# D5035-01.net
KiCad netlist of a schematic drawn in Altium Designer
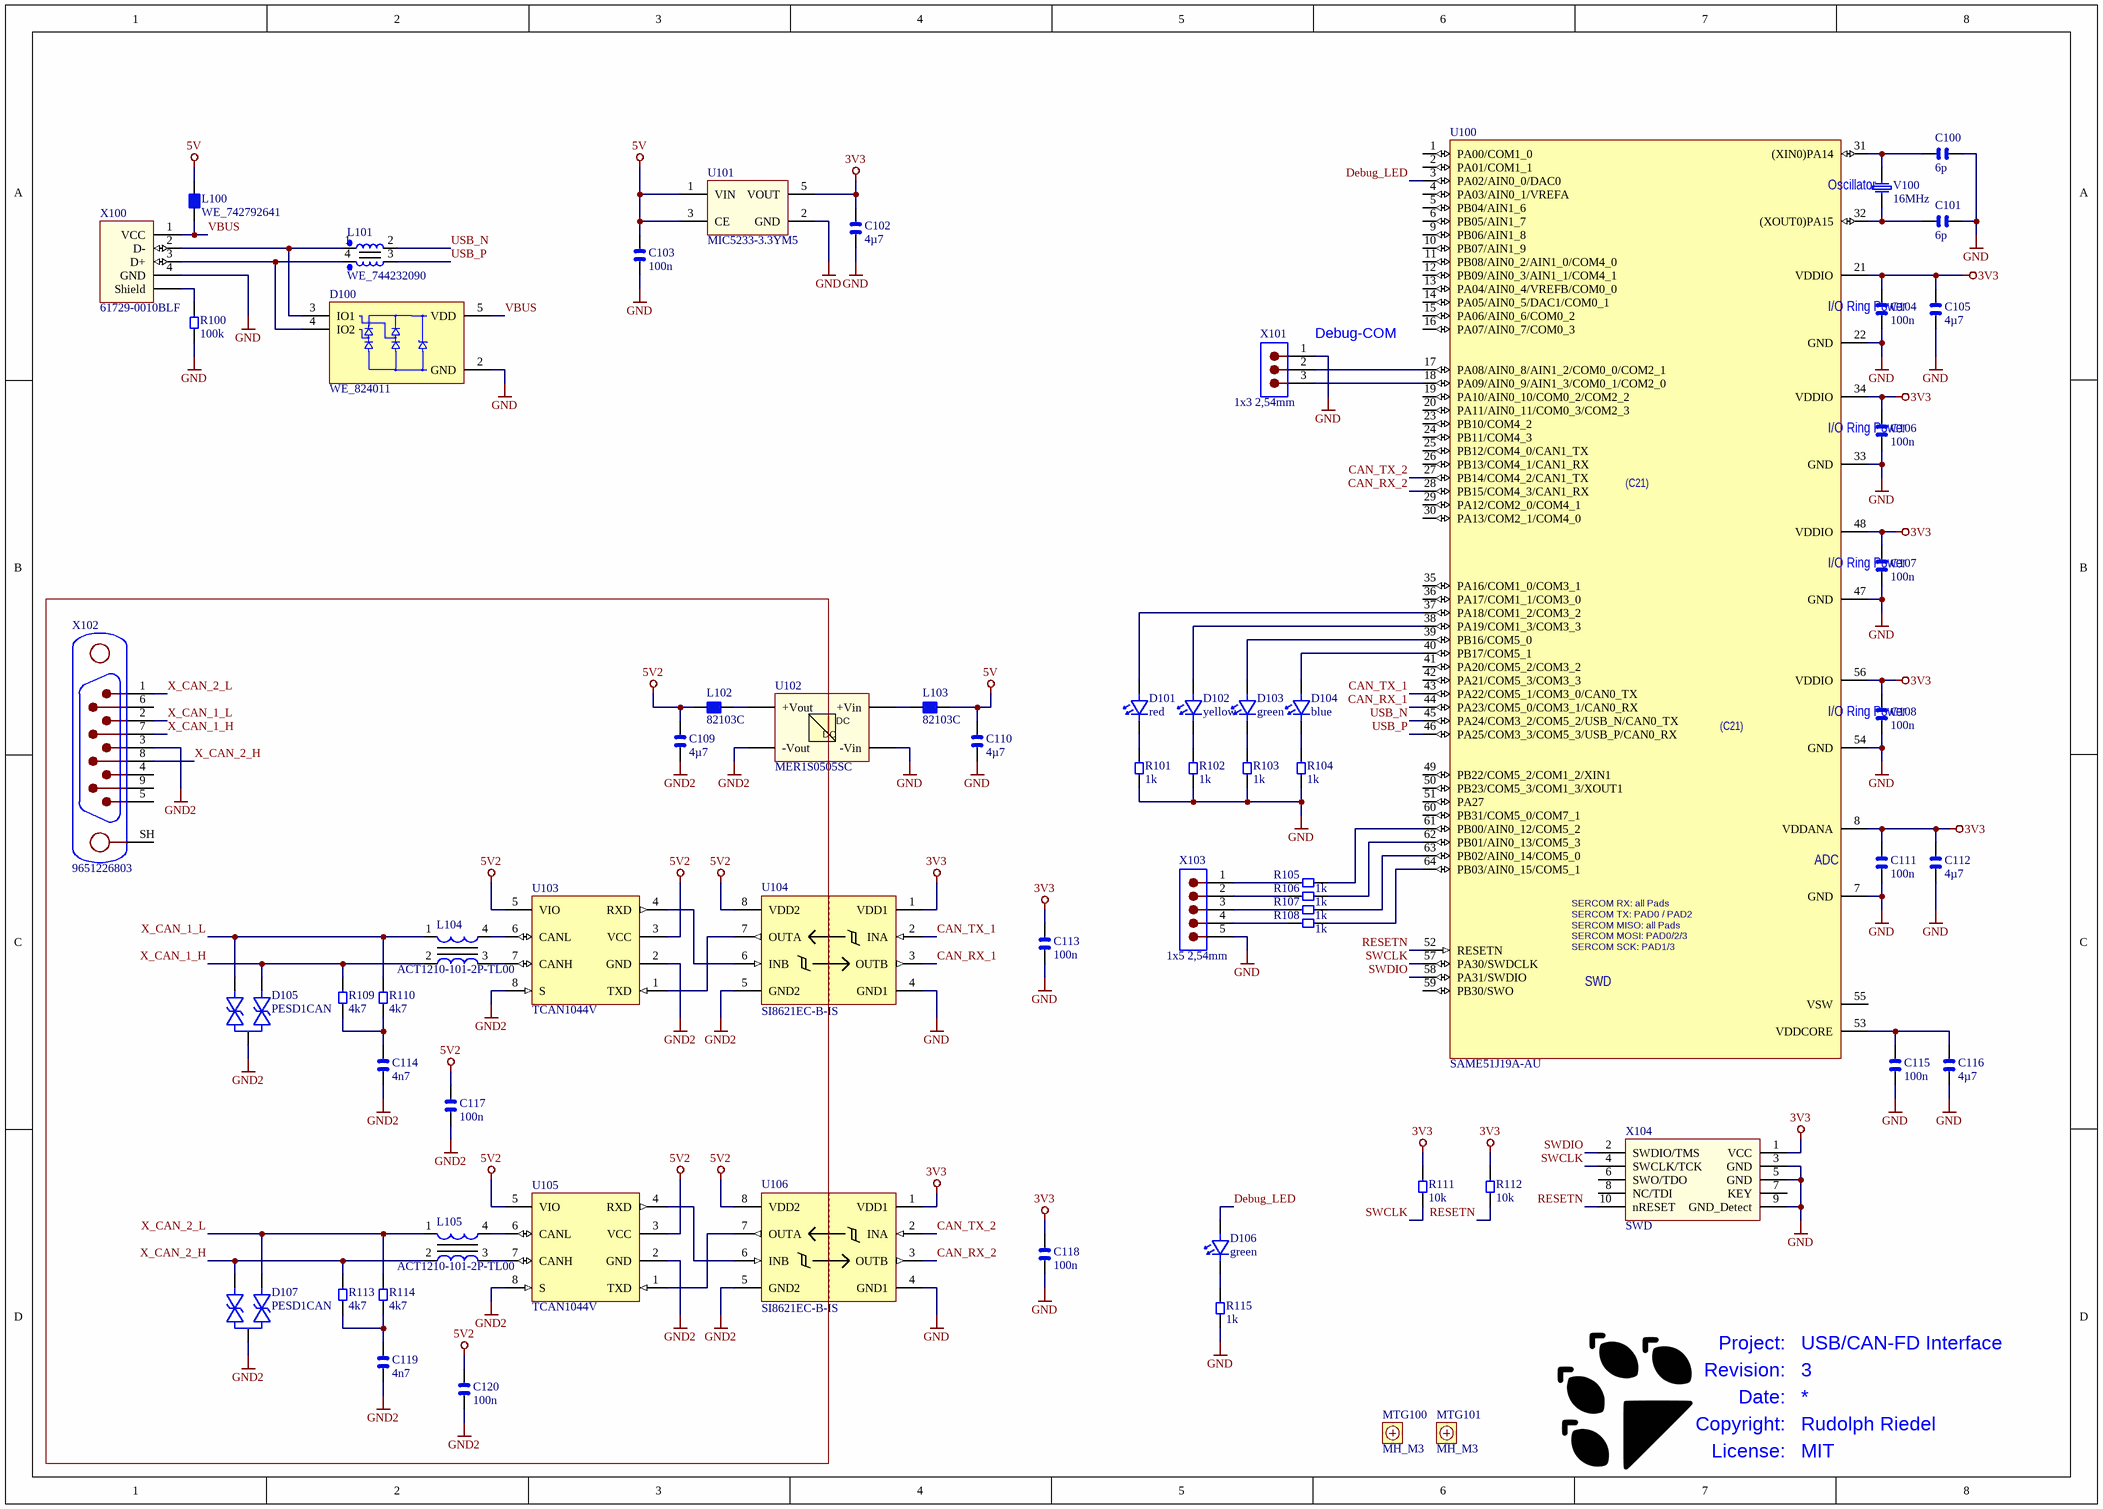
[diagram p0: D5035-01.SchDoc]

(export (version "E")
  (design (tool "Eeschema 10.0.6"))
  (components
    (comp (ref "C100")
      (value "6p")
      (footprint "CAPC1608X09L")
      (description "0603 Chip Capacitor")
      (fields (field (name "PART NUMBER") "CAPC_0603") (field (name "EDITOR") "rriedel"))
      (libsource (lib "HW-Labor_GF") (part "CAP_2_V2"))
    )
    (comp (ref "C101")
      (value "6p")
      (footprint "CAPC1608X09L")
      (description "0603 Chip Capacitor")
      (fields (field (name "PART NUMBER") "CAPC_0603") (field (name "EDITOR") "rriedel"))
      (libsource (lib "HW-Labor_GF") (part "CAP_2_V2"))
    )
    (comp (ref "C102")
      (value "4µ7")
      (footprint "CAPC2012X14L")
      (description "0805 Chip Capacitor")
      (fields (field (name "PART NUMBER") "CAPC_0805") (field (name "EDITOR") "rriedel"))
      (libsource (lib "HW-Labor_GF") (part "CAP_2_V2"))
    )
    (comp (ref "C103")
      (value "100n")
      (footprint "CAPC1608X09L")
      (description "0603 Chip Capacitor")
      (fields (field (name "PART NUMBER") "CAPC_0603") (field (name "EDITOR") "rriedel"))
      (libsource (lib "HW-Labor_GF") (part "CAP_2_V2"))
    )
    (comp (ref "C104")
      (value "100n")
      (footprint "CAPC1608X09L")
      (description "0603 Chip Capacitor")
      (fields (field (name "PART NUMBER") "CAPC_0603") (field (name "EDITOR") "rriedel"))
      (libsource (lib "HW-Labor_GF") (part "CAP_2_V2"))
    )
    (comp (ref "C105")
      (value "4µ7")
      (footprint "CAPC2012X14L")
      (description "0805 Chip Capacitor")
      (fields (field (name "PART NUMBER") "CAPC_0805") (field (name "EDITOR") "rriedel"))
      (libsource (lib "HW-Labor_GF") (part "CAP_2_V2"))
    )
    (comp (ref "C106")
      (value "100n")
      (footprint "CAPC1608X09L")
      (description "0603 Chip Capacitor")
      (fields (field (name "PART NUMBER") "CAPC_0603") (field (name "EDITOR") "rriedel"))
      (libsource (lib "HW-Labor_GF") (part "CAP_2_V2"))
    )
    (comp (ref "C107")
      (value "100n")
      (footprint "CAPC1608X09L")
      (description "0603 Chip Capacitor")
      (fields (field (name "PART NUMBER") "CAPC_0603") (field (name "EDITOR") "rriedel"))
      (libsource (lib "HW-Labor_GF") (part "CAP_2_V2"))
    )
    (comp (ref "C108")
      (value "100n")
      (footprint "CAPC1608X09L")
      (description "0603 Chip Capacitor")
      (fields (field (name "PART NUMBER") "CAPC_0603") (field (name "EDITOR") "rriedel"))
      (libsource (lib "HW-Labor_GF") (part "CAP_2_V2"))
    )
    (comp (ref "C109")
      (value "4µ7")
      (footprint "CAPC2012X14L")
      (description "0805 Chip Capacitor")
      (fields (field (name "PART NUMBER") "CAPC_0805") (field (name "EDITOR") "rriedel"))
      (libsource (lib "HW-Labor_GF") (part "CAP_2_V2"))
    )
    (comp (ref "C110")
      (value "4µ7")
      (footprint "CAPC2012X14L")
      (description "0805 Chip Capacitor")
      (fields (field (name "PART NUMBER") "CAPC_0805") (field (name "EDITOR") "rriedel"))
      (libsource (lib "HW-Labor_GF") (part "CAP_2_V2"))
    )
    (comp (ref "C111")
      (value "100n")
      (footprint "CAPC1608X09L")
      (description "0603 Chip Capacitor")
      (fields (field (name "PART NUMBER") "CAPC_0603") (field (name "EDITOR") "rriedel"))
      (libsource (lib "HW-Labor_GF") (part "CAP_2_V2"))
    )
    (comp (ref "C112")
      (value "4µ7")
      (footprint "CAPC2012X14L")
      (description "0805 Chip Capacitor")
      (fields (field (name "PART NUMBER") "CAPC_0805") (field (name "EDITOR") "rriedel"))
      (libsource (lib "HW-Labor_GF") (part "CAP_2_V2"))
    )
    (comp (ref "C113")
      (value "100n")
      (footprint "CAPC1608X09L")
      (description "0603 Chip Capacitor")
      (fields (field (name "PART NUMBER") "CAPC_0603") (field (name "EDITOR") "rriedel"))
      (libsource (lib "HW-Labor_GF") (part "CAP_2_V2"))
    )
    (comp (ref "C114")
      (value "4n7")
      (footprint "CAPC2012X14L")
      (description "0805 Chip Capacitor")
      (fields (field (name "PART NUMBER") "CAPC_0805") (field (name "EDITOR") "rriedel"))
      (libsource (lib "HW-Labor_GF") (part "CAP_2_V2"))
    )
    (comp (ref "C115")
      (value "100n")
      (footprint "CAPC1608X09L")
      (description "0603 Chip Capacitor")
      (fields (field (name "PART NUMBER") "CAPC_0603") (field (name "EDITOR") "rriedel"))
      (libsource (lib "HW-Labor_GF") (part "CAP_2_V2"))
    )
    (comp (ref "C116")
      (value "4µ7")
      (footprint "CAPC2012X14L")
      (description "0805 Chip Capacitor")
      (fields (field (name "PART NUMBER") "CAPC_0805") (field (name "EDITOR") "rriedel"))
      (libsource (lib "HW-Labor_GF") (part "CAP_2_V2"))
    )
    (comp (ref "C117")
      (value "100n")
      (footprint "CAPC1608X09L")
      (description "0603 Chip Capacitor")
      (fields (field (name "PART NUMBER") "CAPC_0603") (field (name "EDITOR") "rriedel"))
      (libsource (lib "HW-Labor_GF") (part "CAP_2_V2"))
    )
    (comp (ref "C118")
      (value "100n")
      (footprint "CAPC1608X09L")
      (description "0603 Chip Capacitor")
      (fields (field (name "PART NUMBER") "CAPC_0603") (field (name "EDITOR") "rriedel"))
      (libsource (lib "HW-Labor_GF") (part "CAP_2_V2"))
    )
    (comp (ref "C119")
      (value "4n7")
      (footprint "CAPC2012X14L")
      (description "0805 Chip Capacitor")
      (fields (field (name "PART NUMBER") "CAPC_0805") (field (name "EDITOR") "rriedel"))
      (libsource (lib "HW-Labor_GF") (part "CAP_2_V2"))
    )
    (comp (ref "C120")
      (value "100n")
      (footprint "CAPC1608X09L")
      (description "0603 Chip Capacitor")
      (fields (field (name "PART NUMBER") "CAPC_0603") (field (name "EDITOR") "rriedel"))
      (libsource (lib "HW-Labor_GF") (part "CAP_2_V2"))
    )
    (comp (ref "D100")
      (value "WE_824011")
      (footprint "SOT95P280X110-5N")
      (description "TVS Diode Array WE-TVS")
      (fields
        (field (name "MANUFACTURER") "Wuerth")
        (field (name "DISTRIBUTOR_1_PART_NUMBER") "732-4465-1-ND")
        (field (name "EDITOR") "rriedel")
      )
      (libsource (lib "HW-Labor_GF") (part "WE-824011"))
    )
    (comp (ref "D101")
      (value "red")
      (footprint "DIOC1608X06N_LED")
      (description "LED, 0603")
      (fields (field (name "PART NUMBER") "LED_0603") (field (name "EDITOR") "rriedel"))
      (libsource (lib "HW-Labor_GF") (part "LED_generic"))
    )
    (comp (ref "D102")
      (value "yellow")
      (footprint "DIOC1608X06N_LED")
      (description "LED, 0603")
      (fields (field (name "PART NUMBER") "LED_0603") (field (name "EDITOR") "rriedel"))
      (libsource (lib "HW-Labor_GF") (part "LED_generic"))
    )
    (comp (ref "D103")
      (value "green")
      (footprint "DIOC1608X06N_LED")
      (description "LED, 0603")
      (fields (field (name "PART NUMBER") "LED_0603") (field (name "EDITOR") "rriedel"))
      (libsource (lib "HW-Labor_GF") (part "LED_generic"))
    )
    (comp (ref "D104")
      (value "blue")
      (footprint "DIOC1608X06N_LED")
      (description "LED, 0603")
      (fields (field (name "PART NUMBER") "LED_0603") (field (name "EDITOR") "rriedel"))
      (libsource (lib "HW-Labor_GF") (part "LED_generic"))
    )
    (comp (ref "D105")
      (value "PESD1CAN")
      (footprint "SOT95P280X110-3N")
      (description "CAN bus ESD protection diode")
      (fields
        (field (name "MANUFACTURER") "Nexperia")
        (field (name "DISTRIBUTOR_1_PART_NUMBER") "1727-3817-1-ND")
        (field (name "EDITOR") "rriedel")
      )
      (libsource (lib "HW-Labor_GF") (part "PESD1CAN"))
    )
    (comp (ref "D106")
      (value "green")
      (footprint "DIOC1608X06N_LED")
      (description "LED, 0603")
      (fields (field (name "PART NUMBER") "LED_0603") (field (name "EDITOR") "rriedel"))
      (libsource (lib "HW-Labor_GF") (part "LED_generic"))
    )
    (comp (ref "D107")
      (value "PESD1CAN")
      (footprint "SOT95P280X110-3N")
      (description "CAN bus ESD protection diode")
      (fields
        (field (name "MANUFACTURER") "Nexperia")
        (field (name "DISTRIBUTOR_1_PART_NUMBER") "1727-3817-1-ND")
        (field (name "EDITOR") "rriedel")
      )
      (libsource (lib "HW-Labor_GF") (part "PESD1CAN"))
    )
    (comp (ref "L100")
      (value "WE_742792641")
      (footprint "INDC1608X06L")
      (description "SMT EMI suppression ferrite bead WE-CBF")
      (fields
        (field (name "MANUFACTURER") "Wuerth")
        (field (name "DISTRIBUTOR_1_PART_NUMBER") "732-1592-1-ND")
        (field (name "EDITOR") "rriedel")
      )
      (libsource (lib "HW-Labor_GF") (part "IND_2_V1"))
    )
    (comp (ref "L101")
      (value "WE_744232090")
      (footprint "WE_744232090")
      (description "SMD common mode noise suppressor WE-CNSW")
      (fields
        (field (name "MANUFACTURER") "Wuerth")
        (field (name "DISTRIBUTOR_1_PART_NUMBER") "732-1469-1-ND")
        (field (name "EDITOR") "rriedel")
      )
      (libsource (lib "HW-Labor_GF") (part "WE_744232090"))
    )
    (comp (ref "L102")
      (value "82103C")
      (footprint "Murata_8200C")
      (description "10µH, 0,5A, 400mR")
      (fields
        (field (name "MANUFACTURER") "Murata")
        (field (name "DISTRIBUTOR_1_PART_NUMBER") "811-2473-1-ND")
        (field (name "EDITOR") "rriedel")
      )
      (libsource (lib "HW-Labor_GF") (part "IND_2_V1"))
    )
    (comp (ref "L103")
      (value "82103C")
      (footprint "Murata_8200C")
      (description "10µH, 0,5A, 400mR")
      (fields
        (field (name "MANUFACTURER") "Murata")
        (field (name "DISTRIBUTOR_1_PART_NUMBER") "811-2473-1-ND")
        (field (name "EDITOR") "rriedel")
      )
      (libsource (lib "HW-Labor_GF") (part "IND_2_V1"))
    )
    (comp (ref "L104")
      (value "ACT1210-101-2P-TL00")
      (footprint "ACT1210")
      (description "Common Mode Filter,  -50°C ... +150°C, AEC-Q200")
      (fields
        (field (name "MANUFACTURER") "TDK")
        (field (name "DISTRIBUTOR_1_PART_NUMBER") "2442838")
        (field (name "EDITOR") "rriedel")
      )
      (libsource (lib "HW-Labor_GF") (part "CAN_DROSSEL"))
    )
    (comp (ref "L105")
      (value "ACT1210-101-2P-TL00")
      (footprint "ACT1210")
      (description "Common Mode Filter,  -50°C ... +150°C, AEC-Q200")
      (fields
        (field (name "MANUFACTURER") "TDK")
        (field (name "DISTRIBUTOR_1_PART_NUMBER") "2442838")
        (field (name "EDITOR") "rriedel")
      )
      (libsource (lib "HW-Labor_GF") (part "CAN_DROSSEL"))
    )
    (comp (ref "MTG100")
      (value "MH_M3")
      (footprint "HOLE_3_2MM")
      (description "Mounting-Hole for M3 screws")
      (fields (field (name "EDITOR") "rriedel"))
      (libsource (lib "HW-Labor_GF") (part "MTG_V1"))
    )
    (comp (ref "MTG101")
      (value "MH_M3")
      (footprint "HOLE_3_2MM")
      (description "Mounting-Hole for M3 screws")
      (fields (field (name "EDITOR") "rriedel"))
      (libsource (lib "HW-Labor_GF") (part "MTG_V1"))
    )
    (comp (ref "R100")
      (value "100k")
      (footprint "RESC2012X06L")
      (description "0805 Chip Resistor")
      (fields (field (name "PART NUMBER") "RESC_0805") (field (name "EDITOR") "rriedel"))
      (libsource (lib "HW-Labor_GF") (part "RES_2_V2"))
    )
    (comp (ref "R101")
      (value "1k")
      (footprint "RESC1608X06L")
      (description "0603 Chip Resistor")
      (fields (field (name "PART NUMBER") "RESC_0603") (field (name "EDITOR") "rriedel"))
      (libsource (lib "HW-Labor_GF") (part "RES_2_V2"))
    )
    (comp (ref "R102")
      (value "1k")
      (footprint "RESC1608X06L")
      (description "0603 Chip Resistor")
      (fields (field (name "PART NUMBER") "RESC_0603") (field (name "EDITOR") "rriedel"))
      (libsource (lib "HW-Labor_GF") (part "RES_2_V2"))
    )
    (comp (ref "R103")
      (value "1k")
      (footprint "RESC1608X06L")
      (description "0603 Chip Resistor")
      (fields (field (name "PART NUMBER") "RESC_0603") (field (name "EDITOR") "rriedel"))
      (libsource (lib "HW-Labor_GF") (part "RES_2_V2"))
    )
    (comp (ref "R104")
      (value "1k")
      (footprint "RESC1608X06L")
      (description "0603 Chip Resistor")
      (fields (field (name "PART NUMBER") "RESC_0603") (field (name "EDITOR") "rriedel"))
      (libsource (lib "HW-Labor_GF") (part "RES_2_V2"))
    )
    (comp (ref "R105")
      (value "1k")
      (footprint "RESC1608X06L")
      (description "0603 Chip Resistor")
      (fields (field (name "PART NUMBER") "RESC_0603") (field (name "EDITOR") "rriedel"))
      (libsource (lib "HW-Labor_GF") (part "RES_2_V2"))
    )
    (comp (ref "R106")
      (value "1k")
      (footprint "RESC1608X06L")
      (description "0603 Chip Resistor")
      (fields (field (name "PART NUMBER") "RESC_0603") (field (name "EDITOR") "rriedel"))
      (libsource (lib "HW-Labor_GF") (part "RES_2_V2"))
    )
    (comp (ref "R107")
      (value "1k")
      (footprint "RESC1608X06L")
      (description "0603 Chip Resistor")
      (fields (field (name "PART NUMBER") "RESC_0603") (field (name "EDITOR") "rriedel"))
      (libsource (lib "HW-Labor_GF") (part "RES_2_V2"))
    )
    (comp (ref "R108")
      (value "1k")
      (footprint "RESC1608X06L")
      (description "0603 Chip Resistor")
      (fields (field (name "PART NUMBER") "RESC_0603") (field (name "EDITOR") "rriedel"))
      (libsource (lib "HW-Labor_GF") (part "RES_2_V2"))
    )
    (comp (ref "R109")
      (value "4k7")
      (footprint "RESC2012X06L")
      (description "0805 Chip Resistor")
      (fields (field (name "PART NUMBER") "RESC_0805") (field (name "EDITOR") "rriedel"))
      (libsource (lib "HW-Labor_GF") (part "RES_2_V2"))
    )
    (comp (ref "R110")
      (value "4k7")
      (footprint "RESC2012X06L")
      (description "0805 Chip Resistor")
      (fields (field (name "PART NUMBER") "RESC_0805") (field (name "EDITOR") "rriedel"))
      (libsource (lib "HW-Labor_GF") (part "RES_2_V2"))
    )
    (comp (ref "R111")
      (value "10k")
      (footprint "RESC2012X06L")
      (description "0805 Chip Resistor")
      (fields (field (name "PART NUMBER") "RESC_0805") (field (name "EDITOR") "rriedel"))
      (libsource (lib "HW-Labor_GF") (part "RES_2_V2"))
    )
    (comp (ref "R112")
      (value "10k")
      (footprint "RESC2012X06L")
      (description "0805 Chip Resistor")
      (fields (field (name "PART NUMBER") "RESC_0805") (field (name "EDITOR") "rriedel"))
      (libsource (lib "HW-Labor_GF") (part "RES_2_V2"))
    )
    (comp (ref "R113")
      (value "4k7")
      (footprint "RESC2012X06L")
      (description "0805 Chip Resistor")
      (fields (field (name "PART NUMBER") "RESC_0805") (field (name "EDITOR") "rriedel"))
      (libsource (lib "HW-Labor_GF") (part "RES_2_V2"))
    )
    (comp (ref "R114")
      (value "4k7")
      (footprint "RESC2012X06L")
      (description "0805 Chip Resistor")
      (fields (field (name "PART NUMBER") "RESC_0805") (field (name "EDITOR") "rriedel"))
      (libsource (lib "HW-Labor_GF") (part "RES_2_V2"))
    )
    (comp (ref "R115")
      (value "1k")
      (footprint "RESC1608X06L")
      (description "0603 Chip Resistor")
      (fields (field (name "PART NUMBER") "RESC_0603") (field (name "EDITOR") "rriedel"))
      (libsource (lib "HW-Labor_GF") (part "RES_2_V2"))
    )
    (comp (ref "U100")
      (value "SAME51J19A-AU")
      (footprint "TSQFP50P1200X1200X120-64N")
      (description "32-bit Microcontroller, 120MHz Cortex M4-F, 512k FLASH,  2x CAN-FD, -40…85°C")
      (fields
        (field (name "MANUFACTURER") "Microchip")
        (field (name "DISTRIBUTOR_1_PART_NUMBER") "ATSAME51J19A-AUTCT-ND")
        (field (name "EDITOR") "rriedel")
      )
      (libsource (lib "HW-Labor_GF") (part "SAME5xJxxA-AUx"))
    )
    (comp (ref "U101")
      (value "MIC5233-3.3YM5")
      (footprint "SOT95P280X110-5N")
      (description "100 mA LDO,  Vout= 3,3V, -40°C..125°C")
      (fields
        (field (name "PART NUMBER") "MIC5233-3.3")
        (field (name "MANUFACTURER") "Microchip")
        (field (name "EDITOR") "rriedel")
      )
      (libsource (lib "HW-Labor_GF") (part "LDO_SOT23-5"))
    )
    (comp (ref "U102")
      (value "MER1S0505SC")
      (footprint "MER1SxxxxC")
      (description "Isolated 1W Single Output DC-DC Converters 5V/5V 200mA")
      (fields
        (field (name "MANUFACTURER") "Murata")
        (field (name "DISTRIBUTOR_1_PART_NUMBER") "811-2124-5-ND‎")
        (field (name "EDITOR") "rriedel")
      )
      (libsource (lib "HW-Labor_GF") (part "MER1SxxxxC"))
    )
    (comp (ref "U103")
      (value "TCAN1044V")
      (footprint "SOT65P280X100-8N")
      (description "CAN-FD transceiver 8MBit, VIO Pin")
      (fields
        (field (name "MANUFACTURER") "TI")
        (field (name "DISTRIBUTOR_1_PART_NUMBER") "296-TCAN1044VDDFRCT-ND")
        (field (name "EDITOR") "rriedel")
      )
      (libsource (lib "HW-Labor_GF") (part "TJA1051T_3"))
    )
    (comp (ref "U104")
      (value "SI8621EC-B-IS")
      (footprint "SOIC127P600X175-8N")
      (description "Dual channel digital isolator, 150Mbit, 3,75kV")
      (fields
        (field (name "MANUFACTURER") "Silicon Labs")
        (field (name "DISTRIBUTOR_1_PART_NUMBER") "336-4776-1-ND")
        (field (name "EDITOR") "rriedel")
      )
      (libsource (lib "HW-Labor_GF") (part "SI8621"))
    )
    (comp (ref "U105")
      (value "TCAN1044V")
      (footprint "SOT65P280X100-8N")
      (description "CAN-FD transceiver 8MBit, VIO Pin")
      (fields
        (field (name "MANUFACTURER") "TI")
        (field (name "DISTRIBUTOR_1_PART_NUMBER") "296-TCAN1044VDDFRCT-ND")
        (field (name "EDITOR") "rriedel")
      )
      (libsource (lib "HW-Labor_GF") (part "TJA1051T_3"))
    )
    (comp (ref "U106")
      (value "SI8621EC-B-IS")
      (footprint "SOIC127P600X175-8N")
      (description "Dual channel digital isolator, 150Mbit, 3,75kV")
      (fields
        (field (name "MANUFACTURER") "Silicon Labs")
        (field (name "DISTRIBUTOR_1_PART_NUMBER") "336-4776-1-ND")
        (field (name "EDITOR") "rriedel")
      )
      (libsource (lib "HW-Labor_GF") (part "SI8621"))
    )
    (comp (ref "V100")
      (value "16MHz")
      (footprint "NX3225Gx")
      (description "16.000MHz Crystal SMD, 3.2x2.5mm, 8pF, 50ppm,  -40..+150°C")
      (fields
        (field (name "PART NUMBER") "NX3225GB-16.000000MHZ")
        (field (name "MANUFACTURER") "NDK")
        (field (name "EDITOR") "rriedel")
      )
      (libsource (lib "HW-Labor_GF") (part "XTAL_2_V1"))
    )
    (comp (ref "X100")
      (value "61729-0010BLF")
      (footprint "61729-xxxxxLF")
      (description "USB-B socket, THT")
      (fields
        (field (name "MANUFACTURER") "Amphenol")
        (field (name "DISTRIBUTOR_1_PART_NUMBER") "609-1039-ND")
        (field (name "EDITOR") "rriedel")
      )
      (libsource (lib "HW-Labor_GF") (part "USB"))
    )
    (comp (ref "X101")
      (value "1x3 2,54mm")
      (footprint "PINH_1x03_2_54mm")
      (description "Pin-Header 2,54 mm 3pins")
      (fields (field (name "PART NUMBER") "PINH_1x3_2_54") (field (name "EDITOR") "rriedel"))
      (libsource (lib "HW-Labor_GF") (part "CONM_1x3_V2"))
    )
    (comp (ref "X102")
      (value "9651226803")
      (footprint "09651226803")
      (description "D-Sub, 9 pin, male, right angle")
      (fields
        (field (name "MANUFACTURER") "Harting")
        (field (name "DISTRIBUTOR_1_PART_NUMBER") "2752007")
        (field (name "EDITOR") "rriedel")
      )
      (libsource (lib "HW-Labor_GF") (part "D_Sub_9_Male"))
    )
    (comp (ref "X103")
      (value "1x5 2,54mm")
      (footprint "PINH_1x05_2_54mm")
      (description "Pin-Header 2,54 mm 5pins")
      (fields (field (name "PART NUMBER") "PINH_1x5_2_54") (field (name "EDITOR") "rriedel"))
      (libsource (lib "HW-Labor_GF") (part "CONM_1x5_V2"))
    )
    (comp (ref "X104")
      (value "SWD")
      (footprint "FTSH-105-01-L-DV-K")
      (description "ARM Debug-Header 2x5 1,27 mm")
      (fields (field (name "EDITOR") "rriedel"))
      (libsource (lib "HW-Labor_GF") (part "SWD"))
    )
  )
  (nets
    (net (code "1") (name "/CAN_RX_1") (class "Default")
      (node (ref "U100") (pin "44") (pinfunction "PA23/COM5_0/COM3_1/CAN0_RX_44") (pintype "bidirectional"))
      (node (ref "U104") (pin "3") (pinfunction "OUTB_3") (pintype "output"))
    )
    (net (code "2") (name "/CAN_RX_2") (class "Default")
      (node (ref "U100") (pin "28") (pinfunction "PB15/COM4_3/CAN1_RX_28") (pintype "bidirectional"))
      (node (ref "U106") (pin "3") (pinfunction "OUTB_3") (pintype "output"))
    )
    (net (code "3") (name "/CAN_TX_1") (class "Default")
      (node (ref "U100") (pin "43") (pinfunction "PA22/COM5_1/COM3_0/CAN0_TX_43") (pintype "bidirectional"))
      (node (ref "U104") (pin "2") (pinfunction "INA_2") (pintype "input"))
    )
    (net (code "4") (name "/CAN_TX_2") (class "Default")
      (node (ref "U100") (pin "27") (pinfunction "PB14/COM4_2/CAN1_TX_27") (pintype "bidirectional"))
      (node (ref "U106") (pin "2") (pinfunction "INA_2") (pintype "input"))
    )
    (net (code "5") (name "/Debug_LED") (class "Default")
      (node (ref "D106") (pin "2") (pinfunction "2_2") (pintype "passive"))
      (node (ref "U100") (pin "3") (pinfunction "PA02/AIN0_0/DAC0_3") (pintype "bidirectional"))
    )
    (net (code "6") (name "/RESETN") (class "Default")
      (node (ref "R112") (pin "1") (pinfunction "1_1") (pintype "passive"))
      (node (ref "U100") (pin "52") (pinfunction "RESETN_52") (pintype "input"))
      (node (ref "X104") (pin "10") (pinfunction "nRESET_10") (pintype "passive"))
    )
    (net (code "7") (name "/SWCLK") (class "Default")
      (node (ref "R111") (pin "1") (pinfunction "1_1") (pintype "passive"))
      (node (ref "U100") (pin "57") (pinfunction "PA30/SWDCLK_57") (pintype "bidirectional"))
      (node (ref "X104") (pin "4") (pinfunction "SWCLK/TCK_4") (pintype "passive"))
    )
    (net (code "8") (name "/SWDIO") (class "Default")
      (node (ref "U100") (pin "58") (pinfunction "PA31/SWDIO_58") (pintype "bidirectional"))
      (node (ref "X104") (pin "2") (pinfunction "SWDIO/TMS_2") (pintype "passive"))
    )
    (net (code "9") (name "/USB_N") (class "Default")
      (node (ref "L101") (pin "2") (pinfunction "2_2") (pintype "passive"))
      (node (ref "U100") (pin "45") (pinfunction "PA24/COM3_2/COM5_2/USB_N/CAN0_TX_45") (pintype "bidirectional"))
    )
    (net (code "10") (name "/USB_P") (class "Default")
      (node (ref "L101") (pin "3") (pinfunction "3_3") (pintype "passive"))
      (node (ref "U100") (pin "46") (pinfunction "PA25/COM3_3/COM5_3/USB_P/CAN0_RX_46") (pintype "bidirectional"))
    )
    (net (code "11") (name "/VBUS") (class "Default")
      (node (ref "D100") (pin "5") (pinfunction "VDD_5") (pintype "passive"))
      (node (ref "L100") (pin "1") (pinfunction "1_1") (pintype "passive"))
      (node (ref "X100") (pin "1") (pinfunction "VCC_1") (pintype "power_in"))
    )
    (net (code "12") (name "/X_CAN_1_H") (class "Default")
      (node (ref "D105") (pin "2") (pinfunction "2_2") (pintype "passive"))
      (node (ref "L104") (pin "2") (pintype "passive"))
      (node (ref "R109") (pin "2") (pinfunction "2_2") (pintype "passive"))
      (node (ref "X102") (pin "7") (pinfunction "7_7") (pintype "passive"))
    )
    (net (code "13") (name "/X_CAN_1_L") (class "Default")
      (node (ref "D105") (pin "1") (pinfunction "1_1") (pintype "passive"))
      (node (ref "L104") (pin "1") (pintype "passive"))
      (node (ref "R110") (pin "2") (pinfunction "2_2") (pintype "passive"))
      (node (ref "X102") (pin "2") (pinfunction "2_2") (pintype "passive"))
    )
    (net (code "14") (name "/X_CAN_2_H") (class "Default")
      (node (ref "D107") (pin "1") (pinfunction "1_1") (pintype "passive"))
      (node (ref "L105") (pin "2") (pintype "passive"))
      (node (ref "R113") (pin "2") (pinfunction "2_2") (pintype "passive"))
      (node (ref "X102") (pin "8") (pinfunction "8_8") (pintype "passive"))
    )
    (net (code "15") (name "/X_CAN_2_L") (class "Default")
      (node (ref "D107") (pin "2") (pinfunction "2_2") (pintype "passive"))
      (node (ref "L105") (pin "1") (pintype "passive"))
      (node (ref "R114") (pin "2") (pinfunction "2_2") (pintype "passive"))
      (node (ref "X102") (pin "1") (pinfunction "1_1") (pintype "passive"))
    )
    (net (code "16") (name "3V3") (class "Default")
      (node (ref "C102") (pin "2") (pinfunction "2_2") (pintype "passive"))
      (node (ref "C104") (pin "2") (pinfunction "2_2") (pintype "passive"))
      (node (ref "C105") (pin "2") (pinfunction "2_2") (pintype "passive"))
      (node (ref "C106") (pin "2") (pinfunction "2_2") (pintype "passive"))
      (node (ref "C107") (pin "2") (pinfunction "2_2") (pintype "passive"))
      (node (ref "C108") (pin "2") (pinfunction "2_2") (pintype "passive"))
      (node (ref "C111") (pin "2") (pinfunction "2_2") (pintype "passive"))
      (node (ref "C112") (pin "2") (pinfunction "2_2") (pintype "passive"))
      (node (ref "C113") (pin "2") (pinfunction "2_2") (pintype "passive"))
      (node (ref "C118") (pin "2") (pinfunction "2_2") (pintype "passive"))
      (node (ref "R111") (pin "2") (pinfunction "2_2") (pintype "passive"))
      (node (ref "R112") (pin "2") (pinfunction "2_2") (pintype "passive"))
      (node (ref "U100") (pin "21") (pinfunction "VDDIO_21") (pintype "power_in"))
      (node (ref "U100") (pin "34") (pinfunction "VDDIO_34") (pintype "power_in"))
      (node (ref "U100") (pin "48") (pinfunction "VDDIO_48") (pintype "power_in"))
      (node (ref "U100") (pin "56") (pinfunction "VDDIO_56") (pintype "power_in"))
      (node (ref "U100") (pin "8") (pinfunction "VDDANA_8") (pintype "power_in"))
      (node (ref "U101") (pin "5") (pinfunction "VOUT_5") (pintype "passive"))
      (node (ref "U104") (pin "1") (pinfunction "VDD1_1") (pintype "power_in"))
      (node (ref "U106") (pin "1") (pinfunction "VDD1_1") (pintype "power_in"))
      (node (ref "X104") (pin "1") (pinfunction "VCC_1") (pintype "power_in"))
    )
    (net (code "17") (name "5V") (class "Default")
      (node (ref "C103") (pin "2") (pinfunction "2_2") (pintype "passive"))
      (node (ref "C110") (pin "2") (pinfunction "2_2") (pintype "passive"))
      (node (ref "L100") (pin "2") (pinfunction "2_2") (pintype "passive"))
      (node (ref "L103") (pin "1") (pinfunction "1_1") (pintype "passive"))
      (node (ref "U101") (pin "1") (pinfunction "VIN_1") (pintype "passive"))
      (node (ref "U101") (pin "3") (pinfunction "CE_3") (pintype "passive"))
    )
    (net (code "18") (name "5V2") (class "Default")
      (node (ref "C109") (pin "2") (pinfunction "2_2") (pintype "passive"))
      (node (ref "C117") (pin "2") (pinfunction "2_2") (pintype "passive"))
      (node (ref "C120") (pin "2") (pinfunction "2_2") (pintype "passive"))
      (node (ref "L102") (pin "2") (pinfunction "2_2") (pintype "passive"))
      (node (ref "U103") (pin "3") (pinfunction "VCC_3") (pintype "power_in"))
      (node (ref "U103") (pin "5") (pinfunction "VIO_5") (pintype "power_in"))
      (node (ref "U104") (pin "8") (pinfunction "VDD2_8") (pintype "power_in"))
      (node (ref "U105") (pin "3") (pinfunction "VCC_3") (pintype "power_in"))
      (node (ref "U105") (pin "5") (pinfunction "VIO_5") (pintype "power_in"))
      (node (ref "U106") (pin "8") (pinfunction "VDD2_8") (pintype "power_in"))
    )
    (net (code "19") (name "GND") (class "Default")
      (node (ref "C100") (pin "2") (pinfunction "2_2") (pintype "passive"))
      (node (ref "C101") (pin "2") (pinfunction "2_2") (pintype "passive"))
      (node (ref "C102") (pin "1") (pinfunction "1_1") (pintype "passive"))
      (node (ref "C103") (pin "1") (pinfunction "1_1") (pintype "passive"))
      (node (ref "C104") (pin "1") (pinfunction "1_1") (pintype "passive"))
      (node (ref "C105") (pin "1") (pinfunction "1_1") (pintype "passive"))
      (node (ref "C106") (pin "1") (pinfunction "1_1") (pintype "passive"))
      (node (ref "C107") (pin "1") (pinfunction "1_1") (pintype "passive"))
      (node (ref "C108") (pin "1") (pinfunction "1_1") (pintype "passive"))
      (node (ref "C110") (pin "1") (pinfunction "1_1") (pintype "passive"))
      (node (ref "C111") (pin "1") (pinfunction "1_1") (pintype "passive"))
      (node (ref "C112") (pin "1") (pinfunction "1_1") (pintype "passive"))
      (node (ref "C113") (pin "1") (pinfunction "1_1") (pintype "passive"))
      (node (ref "C115") (pin "1") (pinfunction "1_1") (pintype "passive"))
      (node (ref "C116") (pin "1") (pinfunction "1_1") (pintype "passive"))
      (node (ref "C118") (pin "1") (pinfunction "1_1") (pintype "passive"))
      (node (ref "D100") (pin "2") (pinfunction "GND_2") (pintype "passive"))
      (node (ref "R100") (pin "1") (pinfunction "1_1") (pintype "passive"))
      (node (ref "R101") (pin "1") (pinfunction "1_1") (pintype "passive"))
      (node (ref "R102") (pin "1") (pinfunction "1_1") (pintype "passive"))
      (node (ref "R103") (pin "1") (pinfunction "1_1") (pintype "passive"))
      (node (ref "R104") (pin "1") (pinfunction "1_1") (pintype "passive"))
      (node (ref "R115") (pin "1") (pinfunction "1_1") (pintype "passive"))
      (node (ref "U100") (pin "22") (pinfunction "GND_22") (pintype "power_in"))
      (node (ref "U100") (pin "33") (pinfunction "GND_33") (pintype "power_in"))
      (node (ref "U100") (pin "47") (pinfunction "GND_47") (pintype "power_in"))
      (node (ref "U100") (pin "54") (pinfunction "GND_54") (pintype "power_in"))
      (node (ref "U100") (pin "7") (pinfunction "GND_7") (pintype "power_in"))
      (node (ref "U101") (pin "2") (pinfunction "GND_2") (pintype "passive"))
      (node (ref "U102") (pin "2") (pinfunction "-Vin_2") (pintype "power_in"))
      (node (ref "U104") (pin "4") (pinfunction "GND1_4") (pintype "power_in"))
      (node (ref "U106") (pin "4") (pinfunction "GND1_4") (pintype "power_in"))
      (node (ref "X100") (pin "4") (pinfunction "GND_4") (pintype "power_in"))
      (node (ref "X101") (pin "1") (pinfunction "1_1") (pintype "passive"))
      (node (ref "X103") (pin "5") (pinfunction "5_5") (pintype "passive"))
      (node (ref "X104") (pin "3") (pinfunction "GND_3") (pintype "power_in"))
      (node (ref "X104") (pin "5") (pinfunction "GND_5") (pintype "power_in"))
      (node (ref "X104") (pin "9") (pinfunction "GND_Detect_9") (pintype "power_in"))
    )
    (net (code "20") (name "GND2") (class "Default")
      (node (ref "C109") (pin "1") (pinfunction "1_1") (pintype "passive"))
      (node (ref "C114") (pin "1") (pinfunction "1_1") (pintype "passive"))
      (node (ref "C117") (pin "1") (pinfunction "1_1") (pintype "passive"))
      (node (ref "C119") (pin "1") (pinfunction "1_1") (pintype "passive"))
      (node (ref "C120") (pin "1") (pinfunction "1_1") (pintype "passive"))
      (node (ref "D105") (pin "3") (pinfunction "3_3") (pintype "passive"))
      (node (ref "D107") (pin "3") (pinfunction "3_3") (pintype "passive"))
      (node (ref "U102") (pin "4") (pinfunction "-Vout_4") (pintype "power_in"))
      (node (ref "U103") (pin "2") (pinfunction "GND_2") (pintype "power_in"))
      (node (ref "U103") (pin "8") (pinfunction "S_8") (pintype "input"))
      (node (ref "U104") (pin "5") (pinfunction "GND2_5") (pintype "power_in"))
      (node (ref "U105") (pin "2") (pinfunction "GND_2") (pintype "power_in"))
      (node (ref "U105") (pin "8") (pinfunction "S_8") (pintype "input"))
      (node (ref "U106") (pin "5") (pinfunction "GND2_5") (pintype "power_in"))
      (node (ref "X102") (pin "3") (pinfunction "3_3") (pintype "passive"))
    )
    (net (code "21") (name "Net-(C114-Pad2)") (class "Default")
      (node (ref "C114") (pin "2") (pinfunction "2_2") (pintype "passive"))
      (node (ref "R109") (pin "1") (pinfunction "1_1") (pintype "passive"))
      (node (ref "R110") (pin "1") (pinfunction "1_1") (pintype "passive"))
    )
    (net (code "22") (name "Net-(C119-Pad2)") (class "Default")
      (node (ref "C119") (pin "2") (pinfunction "2_2") (pintype "passive"))
      (node (ref "R113") (pin "1") (pinfunction "1_1") (pintype "passive"))
      (node (ref "R114") (pin "1") (pinfunction "1_1") (pintype "passive"))
    )
    (net (code "23") (name "Net-(D100-IO1)") (class "Default")
      (node (ref "D100") (pin "3") (pinfunction "IO1_3") (pintype "passive"))
      (node (ref "L101") (pin "1") (pinfunction "1_1") (pintype "passive"))
      (node (ref "X100") (pin "2") (pinfunction "D-_2") (pintype "bidirectional"))
    )
    (net (code "24") (name "Net-(D100-IO2)") (class "Default")
      (node (ref "D100") (pin "4") (pinfunction "IO2_4") (pintype "passive"))
      (node (ref "L101") (pin "4") (pinfunction "4_4") (pintype "passive"))
      (node (ref "X100") (pin "3") (pinfunction "D+_3") (pintype "bidirectional"))
    )
    (net (code "25") (name "Net-(D101-Pad1)") (class "Default")
      (node (ref "D101") (pin "1") (pinfunction "1_1") (pintype "passive"))
      (node (ref "R101") (pin "2") (pinfunction "2_2") (pintype "passive"))
    )
    (net (code "26") (name "Net-(D102-Pad1)") (class "Default")
      (node (ref "D102") (pin "1") (pinfunction "1_1") (pintype "passive"))
      (node (ref "R102") (pin "2") (pinfunction "2_2") (pintype "passive"))
    )
    (net (code "27") (name "Net-(D103-Pad1)") (class "Default")
      (node (ref "D103") (pin "1") (pinfunction "1_1") (pintype "passive"))
      (node (ref "R103") (pin "2") (pinfunction "2_2") (pintype "passive"))
    )
    (net (code "28") (name "Net-(D104-Pad1)") (class "Default")
      (node (ref "D104") (pin "1") (pinfunction "1_1") (pintype "passive"))
      (node (ref "R104") (pin "2") (pinfunction "2_2") (pintype "passive"))
    )
    (net (code "29") (name "Net-(D106-Pad1)") (class "Default")
      (node (ref "D106") (pin "1") (pinfunction "1_1") (pintype "passive"))
      (node (ref "R115") (pin "2") (pinfunction "2_2") (pintype "passive"))
    )
    (net (code "30") (name "Net-(R105-Pad1)") (class "Default")
      (node (ref "R105") (pin "1") (pinfunction "1_1") (pintype "passive"))
      (node (ref "X103") (pin "1") (pinfunction "1_1") (pintype "passive"))
    )
    (net (code "31") (name "Net-(R106-Pad1)") (class "Default")
      (node (ref "R106") (pin "1") (pinfunction "1_1") (pintype "passive"))
      (node (ref "X103") (pin "2") (pinfunction "2_2") (pintype "passive"))
    )
    (net (code "32") (name "Net-(R107-Pad1)") (class "Default")
      (node (ref "R107") (pin "1") (pinfunction "1_1") (pintype "passive"))
      (node (ref "X103") (pin "3") (pinfunction "3_3") (pintype "passive"))
    )
    (net (code "33") (name "Net-(R108-Pad1)") (class "Default")
      (node (ref "R108") (pin "1") (pinfunction "1_1") (pintype "passive"))
      (node (ref "X103") (pin "4") (pinfunction "4_4") (pintype "passive"))
    )
    (net (code "34") (name "Net-(U100-(XIN0)PA14)") (class "Default")
      (node (ref "C100") (pin "1") (pinfunction "1_1") (pintype "passive"))
      (node (ref "U100") (pin "31") (pinfunction "(XIN0)PA14_31") (pintype "bidirectional"))
      (node (ref "V100") (pin "2") (pinfunction "2_2") (pintype "passive"))
    )
    (net (code "35") (name "Net-(U100-(XOUT0)PA15)") (class "Default")
      (node (ref "C101") (pin "1") (pinfunction "1_1") (pintype "passive"))
      (node (ref "U100") (pin "32") (pinfunction "(XOUT0)PA15_32") (pintype "bidirectional"))
      (node (ref "V100") (pin "1") (pinfunction "1_1") (pintype "passive"))
    )
    (net (code "36") (name "Net-(U100-PA08{slash}AIN0_8{slash}AIN1_2{slash}COM0_0{slash}COM2_1)") (class "Default")
      (node (ref "U100") (pin "17") (pinfunction "PA08/AIN0_8/AIN1_2/COM0_0/COM2_1_17") (pintype "bidirectional"))
      (node (ref "X101") (pin "2") (pinfunction "2_2") (pintype "passive"))
    )
    (net (code "37") (name "Net-(U100-PA09{slash}AIN0_9{slash}AIN1_3{slash}COM0_1{slash}COM2_0)") (class "Default")
      (node (ref "U100") (pin "18") (pinfunction "PA09/AIN0_9/AIN1_3/COM0_1/COM2_0_18") (pintype "bidirectional"))
      (node (ref "X101") (pin "3") (pinfunction "3_3") (pintype "passive"))
    )
    (net (code "38") (name "Net-(U100-PA18{slash}COM1_2{slash}COM3_2)") (class "Default")
      (node (ref "D101") (pin "2") (pinfunction "2_2") (pintype "passive"))
      (node (ref "U100") (pin "37") (pinfunction "PA18/COM1_2/COM3_2_37") (pintype "bidirectional"))
    )
    (net (code "39") (name "Net-(U100-PA19{slash}COM1_3{slash}COM3_3)") (class "Default")
      (node (ref "D102") (pin "2") (pinfunction "2_2") (pintype "passive"))
      (node (ref "U100") (pin "38") (pinfunction "PA19/COM1_3/COM3_3_38") (pintype "bidirectional"))
    )
    (net (code "40") (name "Net-(U100-PB00{slash}AIN0_12{slash}COM5_2)") (class "Default")
      (node (ref "R105") (pin "2") (pinfunction "2_2") (pintype "passive"))
      (node (ref "U100") (pin "61") (pinfunction "PB00/AIN0_12/COM5_2_61") (pintype "bidirectional"))
    )
    (net (code "41") (name "Net-(U100-PB01{slash}AIN0_13{slash}COM5_3)") (class "Default")
      (node (ref "R106") (pin "2") (pinfunction "2_2") (pintype "passive"))
      (node (ref "U100") (pin "62") (pinfunction "PB01/AIN0_13/COM5_3_62") (pintype "bidirectional"))
    )
    (net (code "42") (name "Net-(U100-PB02{slash}AIN0_14{slash}COM5_0)") (class "Default")
      (node (ref "R107") (pin "2") (pinfunction "2_2") (pintype "passive"))
      (node (ref "U100") (pin "63") (pinfunction "PB02/AIN0_14/COM5_0_63") (pintype "bidirectional"))
    )
    (net (code "43") (name "Net-(U100-PB03{slash}AIN0_15{slash}COM5_1)") (class "Default")
      (node (ref "R108") (pin "2") (pinfunction "2_2") (pintype "passive"))
      (node (ref "U100") (pin "64") (pinfunction "PB03/AIN0_15/COM5_1_64") (pintype "bidirectional"))
    )
    (net (code "44") (name "Net-(U100-PB16{slash}COM5_0)") (class "Default")
      (node (ref "D103") (pin "2") (pinfunction "2_2") (pintype "passive"))
      (node (ref "U100") (pin "39") (pinfunction "PB16/COM5_0_39") (pintype "bidirectional"))
    )
    (net (code "45") (name "Net-(U100-PB17{slash}COM5_1)") (class "Default")
      (node (ref "D104") (pin "2") (pinfunction "2_2") (pintype "passive"))
      (node (ref "U100") (pin "40") (pinfunction "PB17/COM5_1_40") (pintype "bidirectional"))
    )
    (net (code "46") (name "Net-(U100-VDDCORE)") (class "Default")
      (node (ref "C115") (pin "2") (pinfunction "2_2") (pintype "passive"))
      (node (ref "C116") (pin "2") (pinfunction "2_2") (pintype "passive"))
      (node (ref "U100") (pin "53") (pinfunction "VDDCORE_53") (pintype "passive"))
    )
    (net (code "47") (name "Net-(U102-+Vin)") (class "Default")
      (node (ref "L103") (pin "2") (pinfunction "2_2") (pintype "passive"))
      (node (ref "U102") (pin "1") (pinfunction "+Vin_1") (pintype "power_in"))
    )
    (net (code "48") (name "Net-(U102-+Vout)") (class "Default")
      (node (ref "L102") (pin "1") (pinfunction "1_1") (pintype "passive"))
      (node (ref "U102") (pin "6") (pinfunction "+Vout_6") (pintype "power_in"))
    )
    (net (code "49") (name "Net-(U103-CANH)") (class "Default")
      (node (ref "L104") (pin "3") (pintype "passive"))
      (node (ref "U103") (pin "7") (pinfunction "CANH_7") (pintype "bidirectional"))
    )
    (net (code "50") (name "Net-(U103-CANL)") (class "Default")
      (node (ref "L104") (pin "4") (pintype "passive"))
      (node (ref "U103") (pin "6") (pinfunction "CANL_6") (pintype "bidirectional"))
    )
    (net (code "51") (name "Net-(U103-RXD)") (class "Default")
      (node (ref "U103") (pin "4") (pinfunction "RXD_4") (pintype "output"))
      (node (ref "U104") (pin "6") (pinfunction "INB_6") (pintype "input"))
    )
    (net (code "52") (name "Net-(U103-TXD)") (class "Default")
      (node (ref "U103") (pin "1") (pinfunction "TXD_1") (pintype "input"))
      (node (ref "U104") (pin "7") (pinfunction "OUTA_7") (pintype "output"))
    )
    (net (code "53") (name "Net-(U105-CANH)") (class "Default")
      (node (ref "L105") (pin "3") (pintype "passive"))
      (node (ref "U105") (pin "7") (pinfunction "CANH_7") (pintype "bidirectional"))
    )
    (net (code "54") (name "Net-(U105-CANL)") (class "Default")
      (node (ref "L105") (pin "4") (pintype "passive"))
      (node (ref "U105") (pin "6") (pinfunction "CANL_6") (pintype "bidirectional"))
    )
    (net (code "55") (name "Net-(U105-RXD)") (class "Default")
      (node (ref "U105") (pin "4") (pinfunction "RXD_4") (pintype "output"))
      (node (ref "U106") (pin "6") (pinfunction "INB_6") (pintype "input"))
    )
    (net (code "56") (name "Net-(U105-TXD)") (class "Default")
      (node (ref "U105") (pin "1") (pinfunction "TXD_1") (pintype "input"))
      (node (ref "U106") (pin "7") (pinfunction "OUTA_7") (pintype "output"))
    )
    (net (code "57") (name "Net-(X100-Shield)") (class "Default")
      (node (ref "R100") (pin "2") (pinfunction "2_2") (pintype "passive"))
      (node (ref "X100") (pin "Shell") (pinfunction "Shield_Shell") (pintype "passive"))
    )
    (net (code "58") (name "unconnected-(U100-PA00{slash}COM1_0-Pad1)") (class "Default")
      (node (ref "U100") (pin "1") (pinfunction "PA00/COM1_0_1") (pintype "bidirectional"))
    )
    (net (code "59") (name "unconnected-(U100-PA01{slash}COM1_1-Pad2)") (class "Default")
      (node (ref "U100") (pin "2") (pinfunction "PA01/COM1_1_2") (pintype "bidirectional"))
    )
    (net (code "60") (name "unconnected-(U100-PA03{slash}AIN0_1{slash}VREFA-Pad4)") (class "Default")
      (node (ref "U100") (pin "4") (pinfunction "PA03/AIN0_1/VREFA_4") (pintype "bidirectional"))
    )
    (net (code "61") (name "unconnected-(U100-PA04{slash}AIN0_4{slash}VREFB{slash}COM0_0-Pad13)") (class "Default")
      (node (ref "U100") (pin "13") (pinfunction "PA04/AIN0_4/VREFB/COM0_0_13") (pintype "bidirectional"))
    )
    (net (code "62") (name "unconnected-(U100-PA05{slash}AIN0_5{slash}DAC1{slash}COM0_1-Pad14)") (class "Default")
      (node (ref "U100") (pin "14") (pinfunction "PA05/AIN0_5/DAC1/COM0_1_14") (pintype "bidirectional"))
    )
    (net (code "63") (name "unconnected-(U100-PA06{slash}AIN0_6{slash}COM0_2-Pad15)") (class "Default")
      (node (ref "U100") (pin "15") (pinfunction "PA06/AIN0_6/COM0_2_15") (pintype "bidirectional"))
    )
    (net (code "64") (name "unconnected-(U100-PA07{slash}AIN0_7{slash}COM0_3-Pad16)") (class "Default")
      (node (ref "U100") (pin "16") (pinfunction "PA07/AIN0_7/COM0_3_16") (pintype "bidirectional"))
    )
    (net (code "65") (name "unconnected-(U100-PA10{slash}AIN0_10{slash}COM0_2{slash}COM2_2-Pad19)") (class "Default")
      (node (ref "U100") (pin "19") (pinfunction "PA10/AIN0_10/COM0_2/COM2_2_19") (pintype "bidirectional"))
    )
    (net (code "66") (name "unconnected-(U100-PA11{slash}AIN0_11{slash}COM0_3{slash}COM2_3-Pad20)") (class "Default")
      (node (ref "U100") (pin "20") (pinfunction "PA11/AIN0_11/COM0_3/COM2_3_20") (pintype "bidirectional"))
    )
    (net (code "67") (name "unconnected-(U100-PA12{slash}COM2_0{slash}COM4_1-Pad29)") (class "Default")
      (node (ref "U100") (pin "29") (pinfunction "PA12/COM2_0/COM4_1_29") (pintype "bidirectional"))
    )
    (net (code "68") (name "unconnected-(U100-PA13{slash}COM2_1{slash}COM4_0-Pad30)") (class "Default")
      (node (ref "U100") (pin "30") (pinfunction "PA13/COM2_1/COM4_0_30") (pintype "bidirectional"))
    )
    (net (code "69") (name "unconnected-(U100-PA16{slash}COM1_0{slash}COM3_1-Pad35)") (class "Default")
      (node (ref "U100") (pin "35") (pinfunction "PA16/COM1_0/COM3_1_35") (pintype "bidirectional"))
    )
    (net (code "70") (name "unconnected-(U100-PA17{slash}COM1_1{slash}COM3_0-Pad36)") (class "Default")
      (node (ref "U100") (pin "36") (pinfunction "PA17/COM1_1/COM3_0_36") (pintype "bidirectional"))
    )
    (net (code "71") (name "unconnected-(U100-PA20{slash}COM5_2{slash}COM3_2-Pad41)") (class "Default")
      (node (ref "U100") (pin "41") (pinfunction "PA20/COM5_2/COM3_2_41") (pintype "bidirectional"))
    )
    (net (code "72") (name "unconnected-(U100-PA21{slash}COM5_3{slash}COM3_3-Pad42)") (class "Default")
      (node (ref "U100") (pin "42") (pinfunction "PA21/COM5_3/COM3_3_42") (pintype "bidirectional"))
    )
    (net (code "73") (name "unconnected-(U100-PA27-Pad51)") (class "Default")
      (node (ref "U100") (pin "51") (pinfunction "PA27_51") (pintype "bidirectional"))
    )
    (net (code "74") (name "unconnected-(U100-PB04{slash}AIN1_6-Pad5)") (class "Default")
      (node (ref "U100") (pin "5") (pinfunction "PB04/AIN1_6_5") (pintype "bidirectional"))
    )
    (net (code "75") (name "unconnected-(U100-PB05{slash}AIN1_7-Pad6)") (class "Default")
      (node (ref "U100") (pin "6") (pinfunction "PB05/AIN1_7_6") (pintype "bidirectional"))
    )
    (net (code "76") (name "unconnected-(U100-PB06{slash}AIN1_8-Pad9)") (class "Default")
      (node (ref "U100") (pin "9") (pinfunction "PB06/AIN1_8_9") (pintype "bidirectional"))
    )
    (net (code "77") (name "unconnected-(U100-PB07{slash}AIN1_9-Pad10)") (class "Default")
      (node (ref "U100") (pin "10") (pinfunction "PB07/AIN1_9_10") (pintype "bidirectional"))
    )
    (net (code "78") (name "unconnected-(U100-PB08{slash}AIN0_2{slash}AIN1_0{slash}COM4_0-Pad11)") (class "Default")
      (node (ref "U100") (pin "11") (pinfunction "PB08/AIN0_2/AIN1_0/COM4_0_11") (pintype "bidirectional"))
    )
    (net (code "79") (name "unconnected-(U100-PB09{slash}AIN0_3{slash}AIN1_1{slash}COM4_1-Pad12)") (class "Default")
      (node (ref "U100") (pin "12") (pinfunction "PB09/AIN0_3/AIN1_1/COM4_1_12") (pintype "bidirectional"))
    )
    (net (code "80") (name "unconnected-(U100-PB10{slash}COM4_2-Pad23)") (class "Default")
      (node (ref "U100") (pin "23") (pinfunction "PB10/COM4_2_23") (pintype "bidirectional"))
    )
    (net (code "81") (name "unconnected-(U100-PB11{slash}COM4_3-Pad24)") (class "Default")
      (node (ref "U100") (pin "24") (pinfunction "PB11/COM4_3_24") (pintype "bidirectional"))
    )
    (net (code "82") (name "unconnected-(U100-PB12{slash}COM4_0{slash}CAN1_TX-Pad25)") (class "Default")
      (node (ref "U100") (pin "25") (pinfunction "PB12/COM4_0/CAN1_TX_25") (pintype "bidirectional"))
    )
    (net (code "83") (name "unconnected-(U100-PB13{slash}COM4_1{slash}CAN1_RX-Pad26)") (class "Default")
      (node (ref "U100") (pin "26") (pinfunction "PB13/COM4_1/CAN1_RX_26") (pintype "bidirectional"))
    )
    (net (code "84") (name "unconnected-(U100-PB22{slash}COM5_2{slash}COM1_2{slash}XIN1-Pad49)") (class "Default")
      (node (ref "U100") (pin "49") (pinfunction "PB22/COM5_2/COM1_2/XIN1_49") (pintype "bidirectional"))
    )
    (net (code "85") (name "unconnected-(U100-PB23{slash}COM5_3{slash}COM1_3{slash}XOUT1-Pad50)") (class "Default")
      (node (ref "U100") (pin "50") (pinfunction "PB23/COM5_3/COM1_3/XOUT1_50") (pintype "bidirectional"))
    )
    (net (code "86") (name "unconnected-(U100-PB30{slash}SWO-Pad59)") (class "Default")
      (node (ref "U100") (pin "59") (pinfunction "PB30/SWO_59") (pintype "bidirectional"))
    )
    (net (code "87") (name "unconnected-(U100-PB31{slash}COM5_0{slash}COM7_1-Pad60)") (class "Default")
      (node (ref "U100") (pin "60") (pinfunction "PB31/COM5_0/COM7_1_60") (pintype "bidirectional"))
    )
    (net (code "88") (name "unconnected-(U100-VSW-Pad55)") (class "Default")
      (node (ref "U100") (pin "55") (pinfunction "VSW_55") (pintype "passive"))
    )
    (net (code "89") (name "unconnected-(X102-Pad4)") (class "Default")
      (node (ref "X102") (pin "4") (pinfunction "4_4") (pintype "passive"))
    )
    (net (code "90") (name "unconnected-(X102-Pad5)") (class "Default")
      (node (ref "X102") (pin "5") (pinfunction "5_5") (pintype "passive"))
    )
    (net (code "91") (name "unconnected-(X102-Pad6)") (class "Default")
      (node (ref "X102") (pin "6") (pinfunction "6_6") (pintype "passive"))
    )
    (net (code "92") (name "unconnected-(X102-Pad9)") (class "Default")
      (node (ref "X102") (pin "9") (pinfunction "9_9") (pintype "passive"))
    )
    (net (code "93") (name "unconnected-(X102-PadSH)") (class "Default")
      (node (ref "X102") (pin "SH") (pinfunction "SH_SH") (pintype "passive"))
    )
    (net (code "94") (name "unconnected-(X104-KEY-Pad7)") (class "Default")
      (node (ref "X104") (pin "7") (pinfunction "KEY_7") (pintype "passive"))
    )
    (net (code "95") (name "unconnected-(X104-NC{slash}TDI-Pad8)") (class "Default")
      (node (ref "X104") (pin "8") (pinfunction "NC/TDI_8") (pintype "passive"))
    )
    (net (code "96") (name "unconnected-(X104-SWO{slash}TDO-Pad6)") (class "Default")
      (node (ref "X104") (pin "6") (pinfunction "SWO/TDO_6") (pintype "passive"))
    )
  )
)
